# Power.net
KiCad netlist of a schematic drawn in Altium Designer
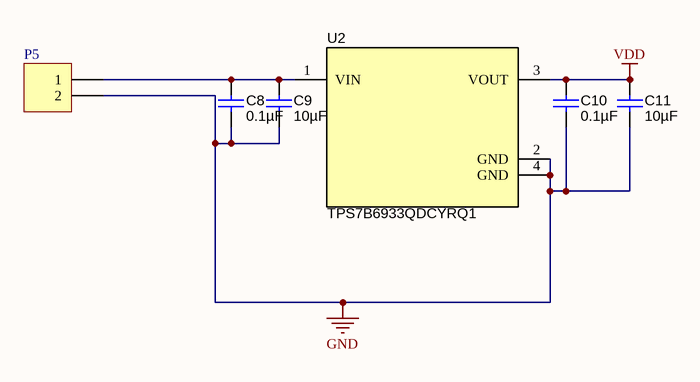
[diagram p0: Power.SchDoc]

(export (version "E")
  (design (tool "Eeschema 10.0.6"))
  (components
    (comp (ref "C8")
      (value "C0603C104J4RACTU")
      (footprint "0603L")
      (description "CAP, CERM, 0.1 µF, 16 V, +/- 5%, X7R, 0603")
      (fields
        (field (name "MANUFACTURER") "Kemet")
        (field (name "VALUEDISPLAYED") "0.1µF")
        (field (name "PUBLISHER") "Texas Instruments")
      )
      (libsource (lib "MDBU014A") (part "C0603C104J4RACTU"))
    )
    (comp (ref "C9")
      (value "GRM32ER71H106KA12L")
      (footprint "1210L")
      (description "CAP, CERM, 10 µF, 50 V, +/- 10%, X7R, 1210")
      (fields
        (field (name "VALUEDISPLAYED") "10µF")
        (field (name "MANUFACTURER") "MuRata")
        (field (name "PUBLISHER") "Texas Instruments")
      )
      (libsource (lib "MDBU014A") (part "GRM32ER71H106KA12L"))
    )
    (comp (ref "C10")
      (value "C0603C104J4RACTU")
      (footprint "0603L")
      (description "CAP, CERM, 0.1 µF, 16 V, +/- 5%, X7R, 0603")
      (fields
        (field (name "MANUFACTURER") "Kemet")
        (field (name "VALUEDISPLAYED") "0.1µF")
        (field (name "PUBLISHER") "Texas Instruments")
      )
      (libsource (lib "MDBU014A") (part "C0603C104J4RACTU"))
    )
    (comp (ref "C11")
      (value "GRM32ER71H106KA12L")
      (footprint "1210L")
      (description "CAP, CERM, 10 µF, 50 V, +/- 10%, X7R, 1210")
      (fields
        (field (name "VALUEDISPLAYED") "10µF")
        (field (name "MANUFACTURER") "MuRata")
        (field (name "PUBLISHER") "Texas Instruments")
      )
      (libsource (lib "MDBU014A") (part "GRM32ER71H106KA12L"))
    )
    (comp (ref "P5")
      (value "~")
      (footprint "HDR1X2")
      (description "Header, 2-Pin")
      (fields (field (name "PUBLISHER") "Altium Limited"))
      (libsource (lib "Miscellaneous Connectors") (part "Header 2"))
    )
    (comp (ref "U2")
      (value "TPS7B6933QDCYRQ1")
      (footprint "DCY0004A_N")
      (description "High Voltage Ultra Low Iq - Low Drop Out Regulator, DCY0004A")
      (fields
        (field (name "MANUFACTURER") "Texas Instruments")
        (field (name "SYMBOLCREATOR") "Altium")
        (field (name "PUBLISHER") "Texas Instruments")
      )
      (libsource (lib "MDBU014A") (part "TPS7B6933QDCYRQ1"))
    )
  )
  (nets
    (net (code "1") (name "GND") (class "Default")
      (node (ref "C10") (pin "2") (pinfunction "2_2") (pintype "passive"))
      (node (ref "C11") (pin "2") (pinfunction "2_2") (pintype "passive"))
      (node (ref "C8") (pin "2") (pinfunction "2_2") (pintype "passive"))
      (node (ref "C9") (pin "2") (pinfunction "2_2") (pintype "passive"))
      (node (ref "P5") (pin "2") (pinfunction "2_2") (pintype "passive"))
      (node (ref "U2") (pin "2") (pinfunction "GND_2") (pintype "power_in"))
      (node (ref "U2") (pin "4") (pinfunction "GND_4") (pintype "power_in"))
    )
    (net (code "2") (name "Net-(U2-VIN)") (class "Default")
      (node (ref "C8") (pin "1") (pinfunction "1_1") (pintype "passive"))
      (node (ref "C9") (pin "1") (pinfunction "1_1") (pintype "passive"))
      (node (ref "P5") (pin "1") (pinfunction "1_1") (pintype "passive"))
      (node (ref "U2") (pin "1") (pinfunction "VIN_1") (pintype "power_in"))
    )
    (net (code "3") (name "VDD") (class "Default")
      (node (ref "C10") (pin "1") (pinfunction "1_1") (pintype "passive"))
      (node (ref "C11") (pin "1") (pinfunction "1_1") (pintype "passive"))
      (node (ref "U2") (pin "3") (pinfunction "VOUT_3") (pintype "power_in"))
    )
  )
)
